# CM_FMC-HPC-AB.net
KiCad netlist of a schematic drawn in Altium Designer
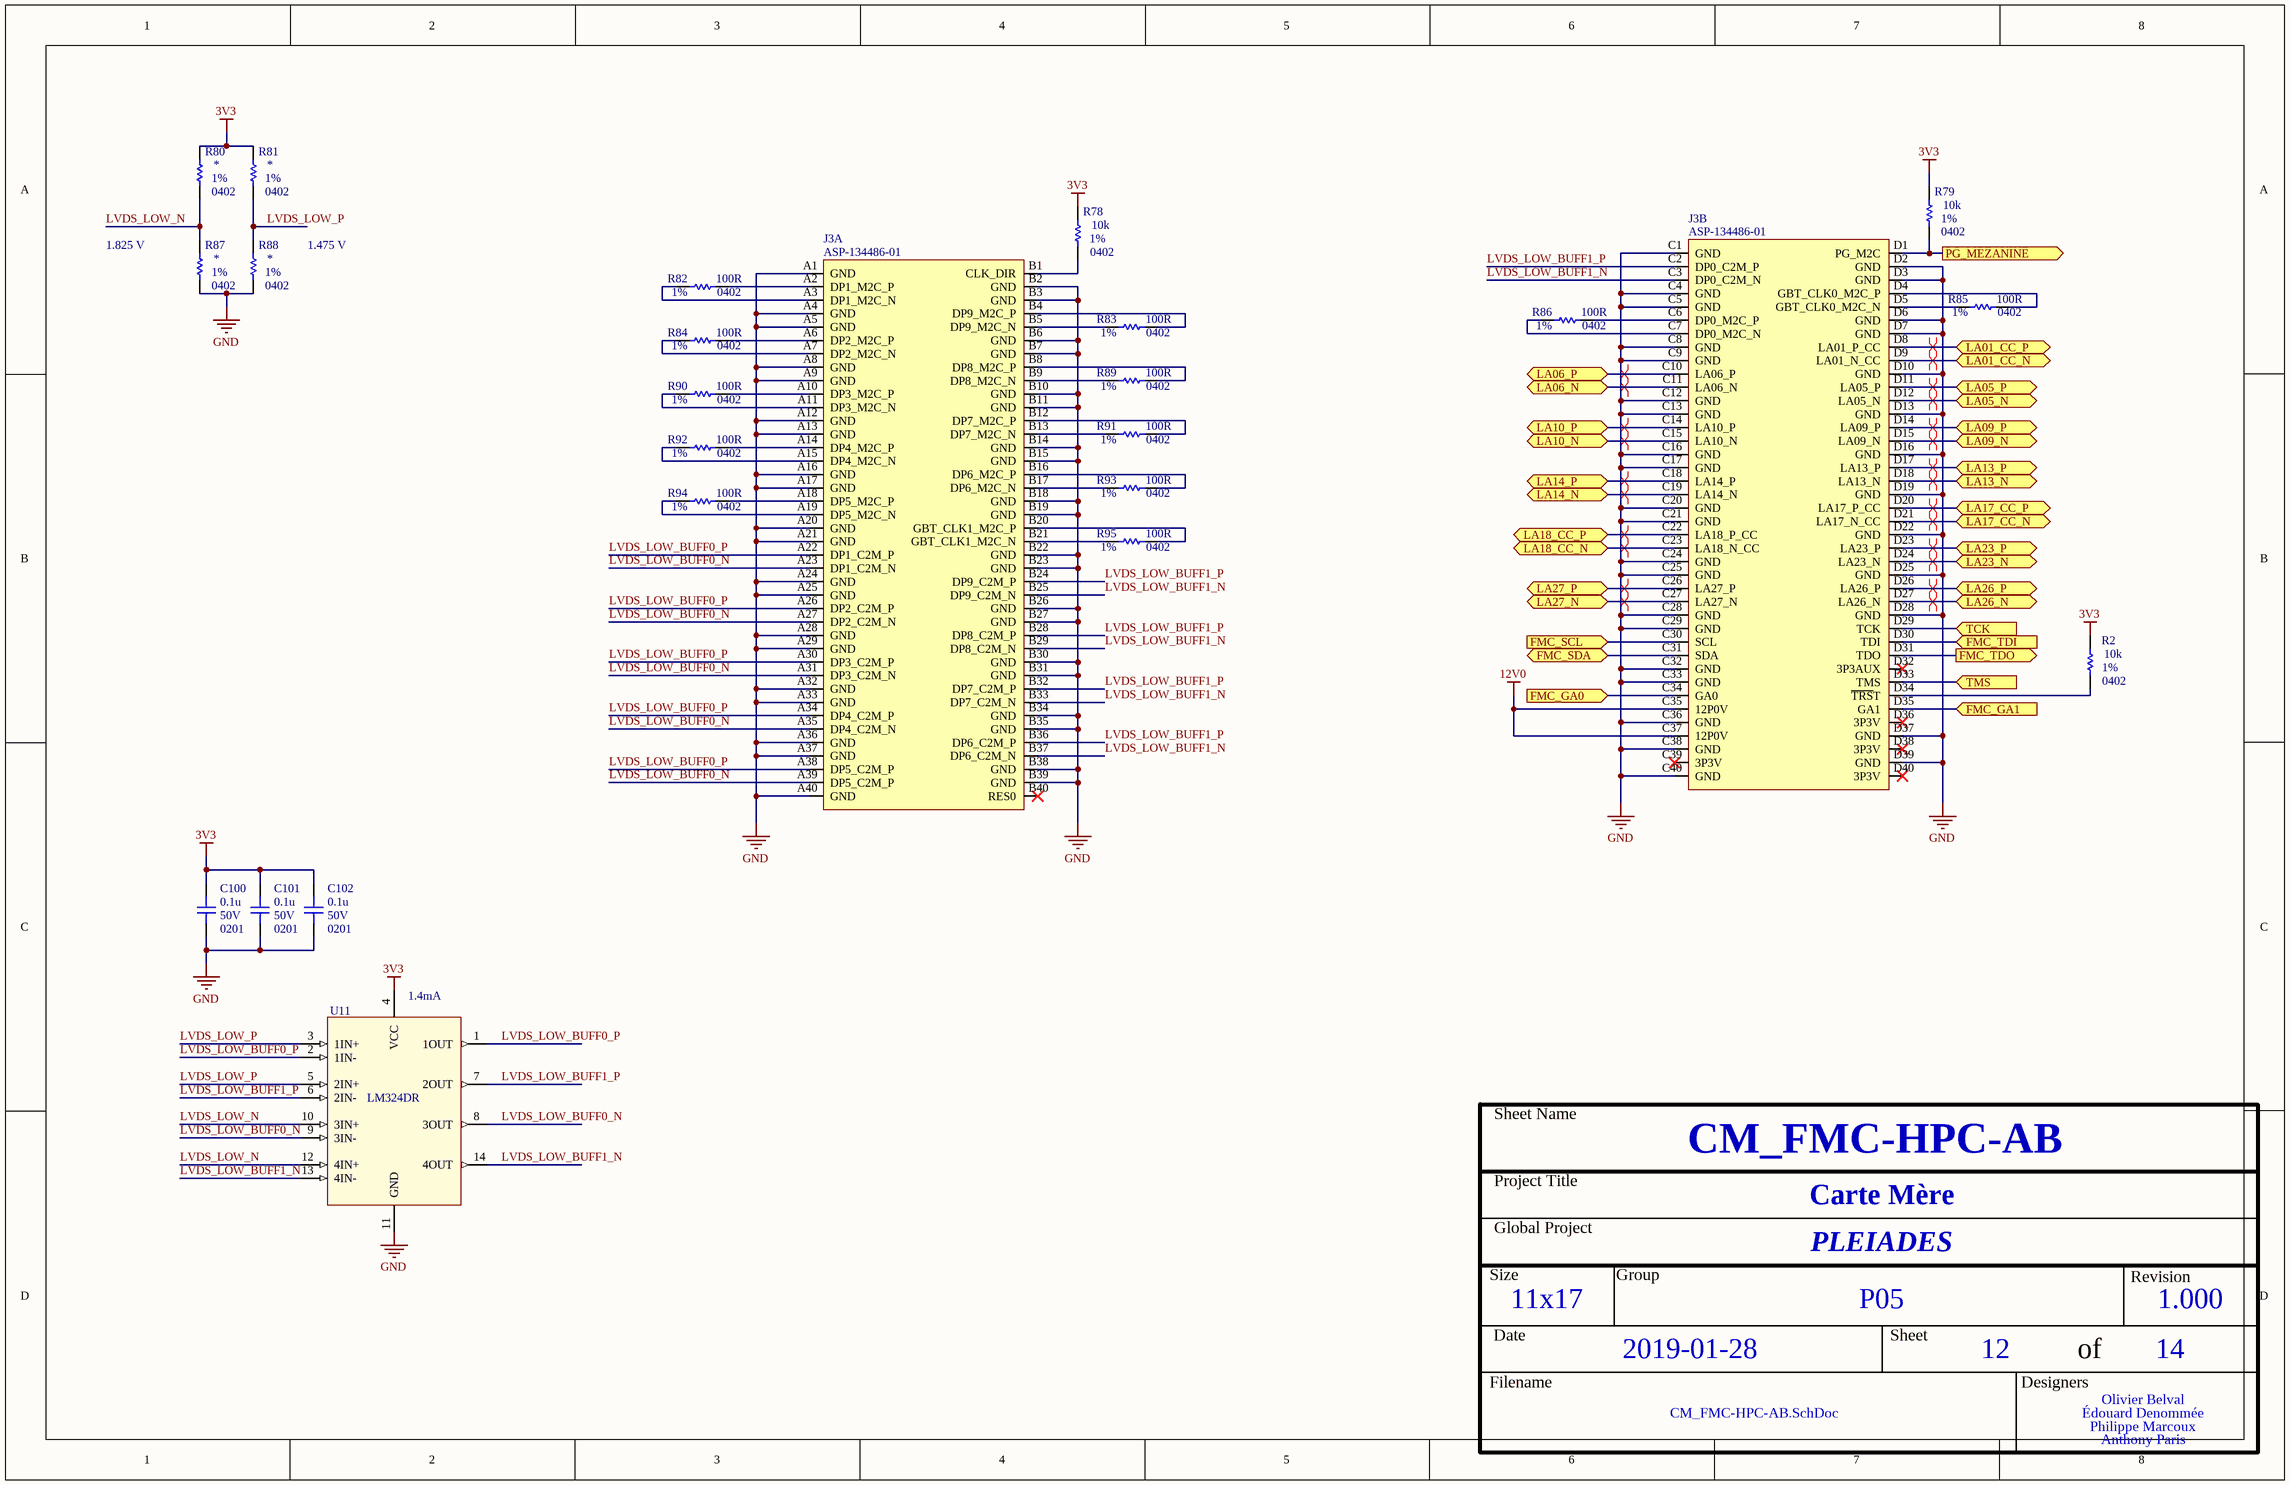
[diagram p0: CM_FMC-HPC-AB.SchDoc]

(export (version "E")
  (design (tool "Eeschema 10.0.6"))
  (components
    (comp (ref "C100")
      (value "0.1u")
      (footprint "CAP_0201")
      (description "CAP - 0201")
      (fields
        (field (name "VOLTAGE") "50V")
        (field (name "PACKAGE") "0201")
        (field (name "CREATEDBY") "Jonathan Bouchard")
      )
      (libsource (lib "S7CAS_Lib2019_REV1_00") (part "CAP - 0201"))
    )
    (comp (ref "C101")
      (value "0.1u")
      (footprint "CAP_0201")
      (description "CAP - 0201")
      (fields
        (field (name "VOLTAGE") "50V")
        (field (name "PACKAGE") "0201")
        (field (name "CREATEDBY") "Jonathan Bouchard")
      )
      (libsource (lib "S7CAS_Lib2019_REV1_00") (part "CAP - 0201"))
    )
    (comp (ref "C102")
      (value "0.1u")
      (footprint "CAP_0201")
      (description "CAP - 0201")
      (fields
        (field (name "VOLTAGE") "50V")
        (field (name "PACKAGE") "0201")
        (field (name "CREATEDBY") "Jonathan Bouchard")
      )
      (libsource (lib "S7CAS_Lib2019_REV1_00") (part "CAP - 0201"))
    )
    (comp (ref "J3")
      (value "ASP-134486-01")
      (footprint "CONN_SAMTEC_ASP-134486-01")
      (description "CONN - VITA 57 MEZZ FEMALE (MOTHERBOARD) HIGH DENSITY - SMD-400")
      (fields
        (field (name "VOLTAGE") "240VAC")
        (field (name "MFG") "Samtec")
        (field (name "CREATEDBY") "Jonathan Bouchard")
      )
      (libsource (lib "S7CAS_Lib2019_REV1_00") (part "CONN_SAMTEC_ASP-134486-01"))
    )
    (comp (ref "R2")
      (value "10k")
      (footprint "RES_0402")
      (description "RES - 0402")
      (fields
        (field (name "VOLTAGE") "50V")
        (field (name "POWER") "1/16W")
        (field (name "PACKAGE") "0402")
        (field (name "PRECISION") "1%")
        (field (name "CREATEDBY") "Jonathan Bouchard")
      )
      (libsource (lib "S7CAS_Lib2019_REV1_00") (part "RES - 0402"))
    )
    (comp (ref "R78")
      (value "10k")
      (footprint "RES_0402")
      (description "RES - 0402")
      (fields
        (field (name "VOLTAGE") "50V")
        (field (name "POWER") "1/16W")
        (field (name "PACKAGE") "0402")
        (field (name "PRECISION") "1%")
        (field (name "CREATEDBY") "Jonathan Bouchard")
      )
      (libsource (lib "S7CAS_Lib2019_REV1_00") (part "RES - 0402"))
    )
    (comp (ref "R79")
      (value "10k")
      (footprint "RES_0402")
      (description "RES - 0402")
      (fields
        (field (name "VOLTAGE") "50V")
        (field (name "POWER") "1/16W")
        (field (name "PACKAGE") "0402")
        (field (name "PRECISION") "1%")
        (field (name "CREATEDBY") "Jonathan Bouchard")
      )
      (libsource (lib "S7CAS_Lib2019_REV1_00") (part "RES - 0402"))
    )
    (comp (ref "R80")
      (value "RES - 0402")
      (footprint "RES_0402")
      (fields
        (field (name "VOLTAGE") "50V")
        (field (name "POWER") "1/16W")
        (field (name "PACKAGE") "0402")
        (field (name "PRECISION") "1%")
        (field (name "ALTIUM_VALUE") "*")
        (field (name "CREATEDBY") "Jonathan Bouchard")
      )
      (libsource (lib "S7CAS_Lib2019_REV1_00") (part "RES - 0402"))
    )
    (comp (ref "R81")
      (value "RES - 0402")
      (footprint "RES_0402")
      (fields
        (field (name "VOLTAGE") "50V")
        (field (name "POWER") "1/16W")
        (field (name "PACKAGE") "0402")
        (field (name "PRECISION") "1%")
        (field (name "ALTIUM_VALUE") "*")
        (field (name "CREATEDBY") "Jonathan Bouchard")
      )
      (libsource (lib "S7CAS_Lib2019_REV1_00") (part "RES - 0402"))
    )
    (comp (ref "R82")
      (value "100R")
      (footprint "RES_0402")
      (description "RES - 0402")
      (fields
        (field (name "VOLTAGE") "50V")
        (field (name "POWER") "1/16W")
        (field (name "PACKAGE") "0402")
        (field (name "PRECISION") "1%")
        (field (name "CREATEDBY") "Jonathan Bouchard")
      )
      (libsource (lib "S7CAS_Lib2019_REV1_00") (part "RES - 0402"))
    )
    (comp (ref "R83")
      (value "100R")
      (footprint "RES_0402")
      (description "RES - 0402")
      (fields
        (field (name "VOLTAGE") "50V")
        (field (name "POWER") "1/16W")
        (field (name "PACKAGE") "0402")
        (field (name "PRECISION") "1%")
        (field (name "CREATEDBY") "Jonathan Bouchard")
      )
      (libsource (lib "S7CAS_Lib2019_REV1_00") (part "RES - 0402"))
    )
    (comp (ref "R84")
      (value "100R")
      (footprint "RES_0402")
      (description "RES - 0402")
      (fields
        (field (name "VOLTAGE") "50V")
        (field (name "POWER") "1/16W")
        (field (name "PACKAGE") "0402")
        (field (name "PRECISION") "1%")
        (field (name "CREATEDBY") "Jonathan Bouchard")
      )
      (libsource (lib "S7CAS_Lib2019_REV1_00") (part "RES - 0402"))
    )
    (comp (ref "R85")
      (value "100R")
      (footprint "RES_0402")
      (description "RES - 0402")
      (fields
        (field (name "VOLTAGE") "50V")
        (field (name "POWER") "1/16W")
        (field (name "PACKAGE") "0402")
        (field (name "PRECISION") "1%")
        (field (name "CREATEDBY") "Jonathan Bouchard")
      )
      (libsource (lib "S7CAS_Lib2019_REV1_00") (part "RES - 0402"))
    )
    (comp (ref "R86")
      (value "100R")
      (footprint "RES_0402")
      (description "RES - 0402")
      (fields
        (field (name "VOLTAGE") "50V")
        (field (name "POWER") "1/16W")
        (field (name "PACKAGE") "0402")
        (field (name "PRECISION") "1%")
        (field (name "CREATEDBY") "Jonathan Bouchard")
      )
      (libsource (lib "S7CAS_Lib2019_REV1_00") (part "RES - 0402"))
    )
    (comp (ref "R87")
      (value "RES - 0402")
      (footprint "RES_0402")
      (fields
        (field (name "VOLTAGE") "50V")
        (field (name "POWER") "1/16W")
        (field (name "PACKAGE") "0402")
        (field (name "PRECISION") "1%")
        (field (name "ALTIUM_VALUE") "*")
        (field (name "CREATEDBY") "Jonathan Bouchard")
      )
      (libsource (lib "S7CAS_Lib2019_REV1_00") (part "RES - 0402"))
    )
    (comp (ref "R88")
      (value "RES - 0402")
      (footprint "RES_0402")
      (fields
        (field (name "VOLTAGE") "50V")
        (field (name "POWER") "1/16W")
        (field (name "PACKAGE") "0402")
        (field (name "PRECISION") "1%")
        (field (name "ALTIUM_VALUE") "*")
        (field (name "CREATEDBY") "Jonathan Bouchard")
      )
      (libsource (lib "S7CAS_Lib2019_REV1_00") (part "RES - 0402"))
    )
    (comp (ref "R89")
      (value "100R")
      (footprint "RES_0402")
      (description "RES - 0402")
      (fields
        (field (name "VOLTAGE") "50V")
        (field (name "POWER") "1/16W")
        (field (name "PACKAGE") "0402")
        (field (name "PRECISION") "1%")
        (field (name "CREATEDBY") "Jonathan Bouchard")
      )
      (libsource (lib "S7CAS_Lib2019_REV1_00") (part "RES - 0402"))
    )
    (comp (ref "R90")
      (value "100R")
      (footprint "RES_0402")
      (description "RES - 0402")
      (fields
        (field (name "VOLTAGE") "50V")
        (field (name "POWER") "1/16W")
        (field (name "PACKAGE") "0402")
        (field (name "PRECISION") "1%")
        (field (name "CREATEDBY") "Jonathan Bouchard")
      )
      (libsource (lib "S7CAS_Lib2019_REV1_00") (part "RES - 0402"))
    )
    (comp (ref "R91")
      (value "100R")
      (footprint "RES_0402")
      (description "RES - 0402")
      (fields
        (field (name "VOLTAGE") "50V")
        (field (name "POWER") "1/16W")
        (field (name "PACKAGE") "0402")
        (field (name "PRECISION") "1%")
        (field (name "CREATEDBY") "Jonathan Bouchard")
      )
      (libsource (lib "S7CAS_Lib2019_REV1_00") (part "RES - 0402"))
    )
    (comp (ref "R92")
      (value "100R")
      (footprint "RES_0402")
      (description "RES - 0402")
      (fields
        (field (name "VOLTAGE") "50V")
        (field (name "POWER") "1/16W")
        (field (name "PACKAGE") "0402")
        (field (name "PRECISION") "1%")
        (field (name "CREATEDBY") "Jonathan Bouchard")
      )
      (libsource (lib "S7CAS_Lib2019_REV1_00") (part "RES - 0402"))
    )
    (comp (ref "R93")
      (value "100R")
      (footprint "RES_0402")
      (description "RES - 0402")
      (fields
        (field (name "VOLTAGE") "50V")
        (field (name "POWER") "1/16W")
        (field (name "PACKAGE") "0402")
        (field (name "PRECISION") "1%")
        (field (name "CREATEDBY") "Jonathan Bouchard")
      )
      (libsource (lib "S7CAS_Lib2019_REV1_00") (part "RES - 0402"))
    )
    (comp (ref "R94")
      (value "100R")
      (footprint "RES_0402")
      (description "RES - 0402")
      (fields
        (field (name "VOLTAGE") "50V")
        (field (name "POWER") "1/16W")
        (field (name "PACKAGE") "0402")
        (field (name "PRECISION") "1%")
        (field (name "CREATEDBY") "Jonathan Bouchard")
      )
      (libsource (lib "S7CAS_Lib2019_REV1_00") (part "RES - 0402"))
    )
    (comp (ref "R95")
      (value "100R")
      (footprint "RES_0402")
      (description "RES - 0402")
      (fields
        (field (name "VOLTAGE") "50V")
        (field (name "POWER") "1/16W")
        (field (name "PACKAGE") "0402")
        (field (name "PRECISION") "1%")
        (field (name "CREATEDBY") "Jonathan Bouchard")
      )
      (libsource (lib "S7CAS_Lib2019_REV1_00") (part "RES - 0402"))
    )
    (comp (ref "U11")
      (value "LM324DR")
      (footprint "LM324DR:SOIC127P600X175-14N")
      (description "OP Amp Quad GP Â±16V/32V 14-Pin SOIC T/R")
      (fields (field (name "DIGI-KEY_PART_NUMBER") "LM324DRRS-ND") (field (name "MF") "Rohm"))
      (libsource (lib "LM324DR") (part "LM324DR"))
    )
  )
  (nets
    (net (code "1") (name "/FMC_GA0") (class "Default")
      (node (ref "J3") (pin "C34") (pinfunction "GA0_C34") (pintype "passive"))
    )
    (net (code "2") (name "/FMC_GA1") (class "Default")
      (node (ref "J3") (pin "D35") (pinfunction "GA1_D35") (pintype "passive"))
    )
    (net (code "3") (name "/FMC_SCL") (class "Default")
      (node (ref "J3") (pin "C30") (pinfunction "SCL_C30") (pintype "passive"))
    )
    (net (code "4") (name "/FMC_SDA") (class "Default")
      (node (ref "J3") (pin "C31") (pinfunction "SDA_C31") (pintype "passive"))
    )
    (net (code "5") (name "/FMC_TDI") (class "Default")
      (node (ref "J3") (pin "D30") (pinfunction "TDI_D30") (pintype "passive"))
    )
    (net (code "6") (name "/FMC_TDO") (class "Default")
      (node (ref "J3") (pin "D31") (pinfunction "TDO_D31") (pintype "passive"))
    )
    (net (code "7") (name "/LA01_CC_N") (class "Default")
      (node (ref "J3") (pin "D9") (pinfunction "LA01_N_CC_D9") (pintype "passive"))
    )
    (net (code "8") (name "/LA01_CC_P") (class "Default")
      (node (ref "J3") (pin "D8") (pinfunction "LA01_P_CC_D8") (pintype "passive"))
    )
    (net (code "9") (name "/LA05_N") (class "Default")
      (node (ref "J3") (pin "D12") (pinfunction "LA05_N_D12") (pintype "passive"))
    )
    (net (code "10") (name "/LA05_P") (class "Default")
      (node (ref "J3") (pin "D11") (pinfunction "LA05_P_D11") (pintype "passive"))
    )
    (net (code "11") (name "/LA06_N") (class "Default")
      (node (ref "J3") (pin "C11") (pinfunction "LA06_N_C11") (pintype "passive"))
    )
    (net (code "12") (name "/LA06_P") (class "Default")
      (node (ref "J3") (pin "C10") (pinfunction "LA06_P_C10") (pintype "passive"))
    )
    (net (code "13") (name "/LA09_N") (class "Default")
      (node (ref "J3") (pin "D15") (pinfunction "LA09_N_D15") (pintype "passive"))
    )
    (net (code "14") (name "/LA09_P") (class "Default")
      (node (ref "J3") (pin "D14") (pinfunction "LA09_P_D14") (pintype "passive"))
    )
    (net (code "15") (name "/LA10_N") (class "Default")
      (node (ref "J3") (pin "C15") (pinfunction "LA10_N_C15") (pintype "passive"))
    )
    (net (code "16") (name "/LA10_P") (class "Default")
      (node (ref "J3") (pin "C14") (pinfunction "LA10_P_C14") (pintype "passive"))
    )
    (net (code "17") (name "/LA13_N") (class "Default")
      (node (ref "J3") (pin "D18") (pinfunction "LA13_N_D18") (pintype "passive"))
    )
    (net (code "18") (name "/LA13_P") (class "Default")
      (node (ref "J3") (pin "D17") (pinfunction "LA13_P_D17") (pintype "passive"))
    )
    (net (code "19") (name "/LA14_N") (class "Default")
      (node (ref "J3") (pin "C19") (pinfunction "LA14_N_C19") (pintype "passive"))
    )
    (net (code "20") (name "/LA14_P") (class "Default")
      (node (ref "J3") (pin "C18") (pinfunction "LA14_P_C18") (pintype "passive"))
    )
    (net (code "21") (name "/LA17_CC_N") (class "Default")
      (node (ref "J3") (pin "D21") (pinfunction "LA17_N_CC_D21") (pintype "passive"))
    )
    (net (code "22") (name "/LA17_CC_P") (class "Default")
      (node (ref "J3") (pin "D20") (pinfunction "LA17_P_CC_D20") (pintype "passive"))
    )
    (net (code "23") (name "/LA18_CC_N") (class "Default")
      (node (ref "J3") (pin "C23") (pinfunction "LA18_N_CC_C23") (pintype "passive"))
    )
    (net (code "24") (name "/LA18_CC_P") (class "Default")
      (node (ref "J3") (pin "C22") (pinfunction "LA18_P_CC_C22") (pintype "passive"))
    )
    (net (code "25") (name "/LA23_N") (class "Default")
      (node (ref "J3") (pin "D24") (pinfunction "LA23_N_D24") (pintype "passive"))
    )
    (net (code "26") (name "/LA23_P") (class "Default")
      (node (ref "J3") (pin "D23") (pinfunction "LA23_P_D23") (pintype "passive"))
    )
    (net (code "27") (name "/LA26_N") (class "Default")
      (node (ref "J3") (pin "D27") (pinfunction "LA26_N_D27") (pintype "passive"))
    )
    (net (code "28") (name "/LA26_P") (class "Default")
      (node (ref "J3") (pin "D26") (pinfunction "LA26_P_D26") (pintype "passive"))
    )
    (net (code "29") (name "/LA27_N") (class "Default")
      (node (ref "J3") (pin "C27") (pinfunction "LA27_N_C27") (pintype "passive"))
    )
    (net (code "30") (name "/LA27_P") (class "Default")
      (node (ref "J3") (pin "C26") (pinfunction "LA27_P_C26") (pintype "passive"))
    )
    (net (code "31") (name "/LVDS_LOW_BUFF0_N") (class "Default")
      (node (ref "J3") (pin "A23") (pinfunction "DP1_C2M_N_A23") (pintype "passive"))
      (node (ref "J3") (pin "A27") (pinfunction "DP2_C2M_N_A27") (pintype "passive"))
      (node (ref "J3") (pin "A31") (pinfunction "DP3_C2M_N_A31") (pintype "passive"))
      (node (ref "J3") (pin "A35") (pinfunction "DP4_C2M_N_A35") (pintype "passive"))
      (node (ref "J3") (pin "A39") (pinfunction "DP5_C2M_P_A39") (pintype "passive"))
      (node (ref "U11") (pin "8") (pinfunction "3OUT_8") (pintype "output"))
      (node (ref "U11") (pin "9") (pinfunction "3IN-_9") (pintype "input"))
    )
    (net (code "32") (name "/LVDS_LOW_BUFF0_P") (class "Default")
      (node (ref "J3") (pin "A22") (pinfunction "DP1_C2M_P_A22") (pintype "passive"))
      (node (ref "J3") (pin "A26") (pinfunction "DP2_C2M_P_A26") (pintype "passive"))
      (node (ref "J3") (pin "A30") (pinfunction "DP3_C2M_P_A30") (pintype "passive"))
      (node (ref "J3") (pin "A34") (pinfunction "DP4_C2M_P_A34") (pintype "passive"))
      (node (ref "J3") (pin "A38") (pinfunction "DP5_C2M_P_A38") (pintype "passive"))
      (node (ref "U11") (pin "1") (pinfunction "1OUT_1") (pintype "output"))
      (node (ref "U11") (pin "2") (pinfunction "1IN-_2") (pintype "input"))
    )
    (net (code "33") (name "/LVDS_LOW_BUFF1_N") (class "Default")
      (node (ref "J3") (pin "B25") (pinfunction "DP9_C2M_N_B25") (pintype "passive"))
      (node (ref "J3") (pin "B29") (pinfunction "DP8_C2M_N_B29") (pintype "passive"))
      (node (ref "J3") (pin "B33") (pinfunction "DP7_C2M_N_B33") (pintype "passive"))
      (node (ref "J3") (pin "B37") (pinfunction "DP6_C2M_N_B37") (pintype "passive"))
      (node (ref "J3") (pin "C3") (pinfunction "DP0_C2M_N_C3") (pintype "passive"))
      (node (ref "U11") (pin "13") (pinfunction "4IN-_13") (pintype "input"))
      (node (ref "U11") (pin "14") (pinfunction "4OUT_14") (pintype "output"))
    )
    (net (code "34") (name "/LVDS_LOW_BUFF1_P") (class "Default")
      (node (ref "J3") (pin "B24") (pinfunction "DP9_C2M_P_B24") (pintype "passive"))
      (node (ref "J3") (pin "B28") (pinfunction "DP8_C2M_P_B28") (pintype "passive"))
      (node (ref "J3") (pin "B32") (pinfunction "DP7_C2M_P_B32") (pintype "passive"))
      (node (ref "J3") (pin "B36") (pinfunction "DP6_C2M_P_B36") (pintype "passive"))
      (node (ref "J3") (pin "C2") (pinfunction "DP0_C2M_P_C2") (pintype "passive"))
      (node (ref "U11") (pin "6") (pinfunction "2IN-_6") (pintype "input"))
      (node (ref "U11") (pin "7") (pinfunction "2OUT_7") (pintype "output"))
    )
    (net (code "35") (name "/LVDS_LOW_N") (class "Default")
      (node (ref "R80") (pin "1") (pinfunction "1_1") (pintype "passive"))
      (node (ref "R87") (pin "2") (pinfunction "2_2") (pintype "passive"))
      (node (ref "U11") (pin "10") (pinfunction "3IN+_10") (pintype "input"))
      (node (ref "U11") (pin "12") (pinfunction "4IN+_12") (pintype "input"))
    )
    (net (code "36") (name "/LVDS_LOW_P") (class "Default")
      (node (ref "R81") (pin "1") (pinfunction "1_1") (pintype "passive"))
      (node (ref "R88") (pin "2") (pinfunction "2_2") (pintype "passive"))
      (node (ref "U11") (pin "3") (pinfunction "1IN+_3") (pintype "input"))
      (node (ref "U11") (pin "5") (pinfunction "2IN+_5") (pintype "input"))
    )
    (net (code "37") (name "/PG_MEZANINE") (class "Default")
      (node (ref "J3") (pin "D1") (pinfunction "PG_M2C_D1") (pintype "passive"))
      (node (ref "R79") (pin "1") (pinfunction "1_1") (pintype "passive"))
    )
    (net (code "38") (name "/TCK") (class "Default")
      (node (ref "J3") (pin "D29") (pinfunction "TCK_D29") (pintype "passive"))
    )
    (net (code "39") (name "/TMS") (class "Default")
      (node (ref "J3") (pin "D33") (pinfunction "TMS_D33") (pintype "passive"))
    )
    (net (code "40") (name "3V3") (class "Default")
      (node (ref "C100") (pin "2") (pinfunction "2_2") (pintype "passive"))
      (node (ref "C101") (pin "2") (pinfunction "2_2") (pintype "passive"))
      (node (ref "C102") (pin "2") (pinfunction "2_2") (pintype "passive"))
      (node (ref "R2") (pin "2") (pinfunction "2_2") (pintype "passive"))
      (node (ref "R78") (pin "2") (pinfunction "2_2") (pintype "passive"))
      (node (ref "R79") (pin "2") (pinfunction "2_2") (pintype "passive"))
      (node (ref "R80") (pin "2") (pinfunction "2_2") (pintype "passive"))
      (node (ref "R81") (pin "2") (pinfunction "2_2") (pintype "passive"))
      (node (ref "U11") (pin "4") (pinfunction "VCC_4") (pintype "power_in"))
    )
    (net (code "41") (name "12V0") (class "Default")
      (node (ref "J3") (pin "C35") (pinfunction "12P0V_C35") (pintype "passive"))
      (node (ref "J3") (pin "C37") (pinfunction "12P0V_C37") (pintype "passive"))
    )
    (net (code "42") (name "GND") (class "Default")
      (node (ref "C100") (pin "1") (pinfunction "1_1") (pintype "passive"))
      (node (ref "C101") (pin "1") (pinfunction "1_1") (pintype "passive"))
      (node (ref "C102") (pin "1") (pinfunction "1_1") (pintype "passive"))
      (node (ref "J3") (pin "A1") (pinfunction "GND_A1") (pintype "passive"))
      (node (ref "J3") (pin "A12") (pinfunction "GND_A12") (pintype "passive"))
      (node (ref "J3") (pin "A13") (pinfunction "GND_A13") (pintype "passive"))
      (node (ref "J3") (pin "A16") (pinfunction "GND_A16") (pintype "passive"))
      (node (ref "J3") (pin "A17") (pinfunction "GND_A17") (pintype "passive"))
      (node (ref "J3") (pin "A20") (pinfunction "GND_A20") (pintype "passive"))
      (node (ref "J3") (pin "A21") (pinfunction "GND_A21") (pintype "passive"))
      (node (ref "J3") (pin "A24") (pinfunction "GND_A24") (pintype "passive"))
      (node (ref "J3") (pin "A25") (pinfunction "GND_A25") (pintype "passive"))
      (node (ref "J3") (pin "A28") (pinfunction "GND_A28") (pintype "passive"))
      (node (ref "J3") (pin "A29") (pinfunction "GND_A29") (pintype "passive"))
      (node (ref "J3") (pin "A32") (pinfunction "GND_A32") (pintype "passive"))
      (node (ref "J3") (pin "A33") (pinfunction "GND_A33") (pintype "passive"))
      (node (ref "J3") (pin "A36") (pinfunction "GND_A36") (pintype "passive"))
      (node (ref "J3") (pin "A37") (pinfunction "GND_A37") (pintype "passive"))
      (node (ref "J3") (pin "A4") (pinfunction "GND_A4") (pintype "passive"))
      (node (ref "J3") (pin "A40") (pinfunction "GND_A40") (pintype "passive"))
      (node (ref "J3") (pin "A5") (pinfunction "GND_A5") (pintype "passive"))
      (node (ref "J3") (pin "A8") (pinfunction "GND_A8") (pintype "passive"))
      (node (ref "J3") (pin "A9") (pinfunction "GND_A9") (pintype "passive"))
      (node (ref "J3") (pin "B10") (pinfunction "GND_B10") (pintype "passive"))
      (node (ref "J3") (pin "B11") (pinfunction "GND_B11") (pintype "passive"))
      (node (ref "J3") (pin "B14") (pinfunction "GND_B14") (pintype "passive"))
      (node (ref "J3") (pin "B15") (pinfunction "GND_B15") (pintype "passive"))
      (node (ref "J3") (pin "B18") (pinfunction "GND_B18") (pintype "passive"))
      (node (ref "J3") (pin "B19") (pinfunction "GND_B19") (pintype "passive"))
      (node (ref "J3") (pin "B2") (pinfunction "GND_B2") (pintype "passive"))
      (node (ref "J3") (pin "B22") (pinfunction "GND_B22") (pintype "passive"))
      (node (ref "J3") (pin "B23") (pinfunction "GND_B23") (pintype "passive"))
      (node (ref "J3") (pin "B26") (pinfunction "GND_B26") (pintype "passive"))
      (node (ref "J3") (pin "B27") (pinfunction "GND_B27") (pintype "passive"))
      (node (ref "J3") (pin "B3") (pinfunction "GND_B3") (pintype "passive"))
      (node (ref "J3") (pin "B30") (pinfunction "GND_B30") (pintype "passive"))
      (node (ref "J3") (pin "B31") (pinfunction "GND_B31") (pintype "passive"))
      (node (ref "J3") (pin "B34") (pinfunction "GND_B34") (pintype "passive"))
      (node (ref "J3") (pin "B35") (pinfunction "GND_B35") (pintype "passive"))
      (node (ref "J3") (pin "B38") (pinfunction "GND_B38") (pintype "passive"))
      (node (ref "J3") (pin "B39") (pinfunction "GND_B39") (pintype "passive"))
      (node (ref "J3") (pin "B6") (pinfunction "GND_B6") (pintype "passive"))
      (node (ref "J3") (pin "B7") (pinfunction "GND_B7") (pintype "passive"))
      (node (ref "J3") (pin "C1") (pinfunction "GND_C1") (pintype "passive"))
      (node (ref "J3") (pin "C12") (pinfunction "GND_C12") (pintype "passive"))
      (node (ref "J3") (pin "C13") (pinfunction "GND_C13") (pintype "passive"))
      (node (ref "J3") (pin "C16") (pinfunction "GND_C16") (pintype "passive"))
      (node (ref "J3") (pin "C17") (pinfunction "GND_C17") (pintype "passive"))
      (node (ref "J3") (pin "C20") (pinfunction "GND_C20") (pintype "passive"))
      (node (ref "J3") (pin "C21") (pinfunction "GND_C21") (pintype "passive"))
      (node (ref "J3") (pin "C24") (pinfunction "GND_C24") (pintype "passive"))
      (node (ref "J3") (pin "C25") (pinfunction "GND_C25") (pintype "passive"))
      (node (ref "J3") (pin "C28") (pinfunction "GND_C28") (pintype "passive"))
      (node (ref "J3") (pin "C29") (pinfunction "GND_C29") (pintype "passive"))
      (node (ref "J3") (pin "C32") (pinfunction "GND_C32") (pintype "passive"))
      (node (ref "J3") (pin "C33") (pinfunction "GND_C33") (pintype "passive"))
      (node (ref "J3") (pin "C36") (pinfunction "GND_C36") (pintype "passive"))
      (node (ref "J3") (pin "C38") (pinfunction "GND_C38") (pintype "passive"))
      (node (ref "J3") (pin "C4") (pinfunction "GND_C4") (pintype "passive"))
      (node (ref "J3") (pin "C40") (pinfunction "GND_C40") (pintype "passive"))
      (node (ref "J3") (pin "C5") (pinfunction "GND_C5") (pintype "passive"))
      (node (ref "J3") (pin "C8") (pinfunction "GND_C8") (pintype "passive"))
      (node (ref "J3") (pin "C9") (pinfunction "GND_C9") (pintype "passive"))
      (node (ref "J3") (pin "D10") (pinfunction "GND_D10") (pintype "passive"))
      (node (ref "J3") (pin "D13") (pinfunction "GND_D13") (pintype "passive"))
      (node (ref "J3") (pin "D16") (pinfunction "GND_D16") (pintype "passive"))
      (node (ref "J3") (pin "D19") (pinfunction "GND_D19") (pintype "passive"))
      (node (ref "J3") (pin "D2") (pinfunction "GND_D2") (pintype "passive"))
      (node (ref "J3") (pin "D22") (pinfunction "GND_D22") (pintype "passive"))
      (node (ref "J3") (pin "D25") (pinfunction "GND_D25") (pintype "passive"))
      (node (ref "J3") (pin "D28") (pinfunction "GND_D28") (pintype "passive"))
      (node (ref "J3") (pin "D3") (pinfunction "GND_D3") (pintype "passive"))
      (node (ref "J3") (pin "D37") (pinfunction "GND_D37") (pintype "passive"))
      (node (ref "J3") (pin "D39") (pinfunction "GND_D39") (pintype "passive"))
      (node (ref "J3") (pin "D6") (pinfunction "GND_D6") (pintype "passive"))
      (node (ref "J3") (pin "D7") (pinfunction "GND_D7") (pintype "passive"))
      (node (ref "R87") (pin "1") (pinfunction "1_1") (pintype "passive"))
      (node (ref "R88") (pin "1") (pinfunction "1_1") (pintype "passive"))
      (node (ref "U11") (pin "11") (pinfunction "GND_11") (pintype "passive"))
    )
    (net (code "43") (name "Net-(J3A-CLK_DIR)") (class "Default")
      (node (ref "J3") (pin "B1") (pinfunction "CLK_DIR_B1") (pintype "passive"))
      (node (ref "R78") (pin "1") (pinfunction "1_1") (pintype "passive"))
    )
    (net (code "44") (name "Net-(J3A-DP1_M2C_N)") (class "Default")
      (node (ref "J3") (pin "A3") (pinfunction "DP1_M2C_N_A3") (pintype "passive"))
      (node (ref "R82") (pin "2") (pinfunction "2_2") (pintype "passive"))
    )
    (net (code "45") (name "Net-(J3A-DP1_M2C_P)") (class "Default")
      (node (ref "J3") (pin "A2") (pinfunction "DP1_M2C_P_A2") (pintype "passive"))
      (node (ref "R82") (pin "1") (pinfunction "1_1") (pintype "passive"))
    )
    (net (code "46") (name "Net-(J3A-DP2_M2C_N)") (class "Default")
      (node (ref "J3") (pin "A7") (pinfunction "DP2_M2C_N_A7") (pintype "passive"))
      (node (ref "R84") (pin "2") (pinfunction "2_2") (pintype "passive"))
    )
    (net (code "47") (name "Net-(J3A-DP2_M2C_P)") (class "Default")
      (node (ref "J3") (pin "A6") (pinfunction "DP2_M2C_P_A6") (pintype "passive"))
      (node (ref "R84") (pin "1") (pinfunction "1_1") (pintype "passive"))
    )
    (net (code "48") (name "Net-(J3A-DP3_M2C_N)") (class "Default")
      (node (ref "J3") (pin "A11") (pinfunction "DP3_M2C_N_A11") (pintype "passive"))
      (node (ref "R90") (pin "2") (pinfunction "2_2") (pintype "passive"))
    )
    (net (code "49") (name "Net-(J3A-DP3_M2C_P)") (class "Default")
      (node (ref "J3") (pin "A10") (pinfunction "DP3_M2C_P_A10") (pintype "passive"))
      (node (ref "R90") (pin "1") (pinfunction "1_1") (pintype "passive"))
    )
    (net (code "50") (name "Net-(J3A-DP4_M2C_N)") (class "Default")
      (node (ref "J3") (pin "A15") (pinfunction "DP4_M2C_N_A15") (pintype "passive"))
      (node (ref "R92") (pin "2") (pinfunction "2_2") (pintype "passive"))
    )
    (net (code "51") (name "Net-(J3A-DP4_M2C_P)") (class "Default")
      (node (ref "J3") (pin "A14") (pinfunction "DP4_M2C_P_A14") (pintype "passive"))
      (node (ref "R92") (pin "1") (pinfunction "1_1") (pintype "passive"))
    )
    (net (code "52") (name "Net-(J3A-DP5_M2C_N)") (class "Default")
      (node (ref "J3") (pin "A19") (pinfunction "DP5_M2C_N_A19") (pintype "passive"))
      (node (ref "R94") (pin "2") (pinfunction "2_2") (pintype "passive"))
    )
    (net (code "53") (name "Net-(J3A-DP5_M2C_P)") (class "Default")
      (node (ref "J3") (pin "A18") (pinfunction "DP5_M2C_P_A18") (pintype "passive"))
      (node (ref "R94") (pin "1") (pinfunction "1_1") (pintype "passive"))
    )
    (net (code "54") (name "Net-(J3A-DP6_M2C_N)") (class "Default")
      (node (ref "J3") (pin "B17") (pinfunction "DP6_M2C_N_B17") (pintype "passive"))
      (node (ref "R93") (pin "1") (pinfunction "1_1") (pintype "passive"))
    )
    (net (code "55") (name "Net-(J3A-DP6_M2C_P)") (class "Default")
      (node (ref "J3") (pin "B16") (pinfunction "DP6_M2C_P_B16") (pintype "passive"))
      (node (ref "R93") (pin "2") (pinfunction "2_2") (pintype "passive"))
    )
    (net (code "56") (name "Net-(J3A-DP7_M2C_N)") (class "Default")
      (node (ref "J3") (pin "B13") (pinfunction "DP7_M2C_N_B13") (pintype "passive"))
      (node (ref "R91") (pin "1") (pinfunction "1_1") (pintype "passive"))
    )
    (net (code "57") (name "Net-(J3A-DP7_M2C_P)") (class "Default")
      (node (ref "J3") (pin "B12") (pinfunction "DP7_M2C_P_B12") (pintype "passive"))
      (node (ref "R91") (pin "2") (pinfunction "2_2") (pintype "passive"))
    )
    (net (code "58") (name "Net-(J3A-DP8_M2C_N)") (class "Default")
      (node (ref "J3") (pin "B9") (pinfunction "DP8_M2C_N_B9") (pintype "passive"))
      (node (ref "R89") (pin "1") (pinfunction "1_1") (pintype "passive"))
    )
    (net (code "59") (name "Net-(J3A-DP8_M2C_P)") (class "Default")
      (node (ref "J3") (pin "B8") (pinfunction "DP8_M2C_P_B8") (pintype "passive"))
      (node (ref "R89") (pin "2") (pinfunction "2_2") (pintype "passive"))
    )
    (net (code "60") (name "Net-(J3A-DP9_M2C_N)") (class "Default")
      (node (ref "J3") (pin "B5") (pinfunction "DP9_M2C_N_B5") (pintype "passive"))
      (node (ref "R83") (pin "1") (pinfunction "1_1") (pintype "passive"))
    )
    (net (code "61") (name "Net-(J3A-DP9_M2C_P)") (class "Default")
      (node (ref "J3") (pin "B4") (pinfunction "DP9_M2C_P_B4") (pintype "passive"))
      (node (ref "R83") (pin "2") (pinfunction "2_2") (pintype "passive"))
    )
    (net (code "62") (name "Net-(J3A-GBT_CLK1_M2C_N)") (class "Default")
      (node (ref "J3") (pin "B21") (pinfunction "GBT_CLK1_M2C_N_B21") (pintype "passive"))
      (node (ref "R95") (pin "1") (pinfunction "1_1") (pintype "passive"))
    )
    (net (code "63") (name "Net-(J3A-GBT_CLK1_M2C_P)") (class "Default")
      (node (ref "J3") (pin "B20") (pinfunction "GBT_CLK1_M2C_P_B20") (pintype "passive"))
      (node (ref "R95") (pin "2") (pinfunction "2_2") (pintype "passive"))
    )
    (net (code "64") (name "Net-(J3B-DP0_M2C_N)") (class "Default")
      (node (ref "J3") (pin "C7") (pinfunction "DP0_M2C_N_C7") (pintype "passive"))
      (node (ref "R86") (pin "2") (pinfunction "2_2") (pintype "passive"))
    )
    (net (code "65") (name "Net-(J3B-DP0_M2C_P)") (class "Default")
      (node (ref "J3") (pin "C6") (pinfunction "DP0_M2C_P_C6") (pintype "passive"))
      (node (ref "R86") (pin "1") (pinfunction "1_1") (pintype "passive"))
    )
    (net (code "66") (name "Net-(J3B-GBT_CLK0_M2C_N)") (class "Default")
      (node (ref "J3") (pin "D5") (pinfunction "GBT_CLK0_M2C_N_D5") (pintype "passive"))
      (node (ref "R85") (pin "1") (pinfunction "1_1") (pintype "passive"))
    )
    (net (code "67") (name "Net-(J3B-GBT_CLK0_M2C_P)") (class "Default")
      (node (ref "J3") (pin "D4") (pinfunction "GBT_CLK0_M2C_P_D4") (pintype "passive"))
      (node (ref "R85") (pin "2") (pinfunction "2_2") (pintype "passive"))
    )
    (net (code "68") (name "Net-(J3B-~{TRS}T)") (class "Default")
      (node (ref "J3") (pin "D34") (pinfunction "~{TRS}T_D34") (pintype "passive"))
      (node (ref "R2") (pin "1") (pinfunction "1_1") (pintype "passive"))
    )
    (net (code "69") (name "unconnected-(J3A-RES0-PadB40)") (class "Default")
      (node (ref "J3") (pin "B40") (pinfunction "RES0_B40") (pintype "passive+no_connect"))
    )
    (net (code "70") (name "unconnected-(J3B-3P3AUX-PadD32)") (class "Default")
      (node (ref "J3") (pin "D32") (pinfunction "3P3AUX_D32") (pintype "passive+no_connect"))
    )
    (net (code "71") (name "unconnected-(J3B-3P3V-PadC39)") (class "Default")
      (node (ref "J3") (pin "C39") (pinfunction "3P3V_C39") (pintype "passive+no_connect"))
    )
    (net (code "72") (name "unconnected-(J3B-3P3V-PadD36)") (class "Default")
      (node (ref "J3") (pin "D36") (pinfunction "3P3V_D36") (pintype "passive+no_connect"))
    )
    (net (code "73") (name "unconnected-(J3B-3P3V-PadD38)") (class "Default")
      (node (ref "J3") (pin "D38") (pinfunction "3P3V_D38") (pintype "passive+no_connect"))
    )
    (net (code "74") (name "unconnected-(J3B-3P3V-PadD40)") (class "Default")
      (node (ref "J3") (pin "D40") (pinfunction "3P3V_D40") (pintype "passive+no_connect"))
    )
  )
)
